# microwaveBoardSimple.net
KiCad netlist of a schematic drawn in Altium Designer
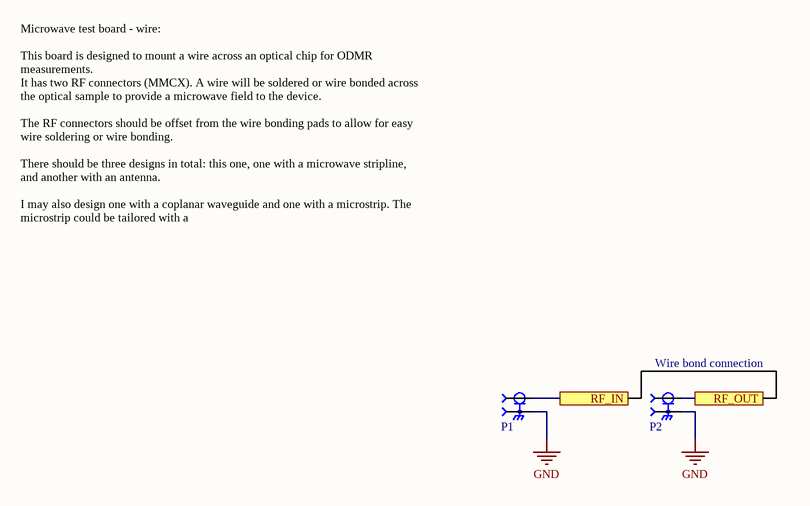
[diagram p0: microwaveBoardSimple.SchDoc]

(export (version "E")
  (design (tool "Eeschema 10.0.6"))
  (components
    (comp (ref "P1")
      (value "MMCXV-J-P-HF-ST-EM1")
      (footprint "MMCXV-J-P-HF-ST-EM1")
      (description "50 OHM MMCX HIGH-VIBRATION JACK,")
      (fields (field (name "PART NUMBER") "PXX-SAM-00013") (field (name "PUBLISHER") "AlbertaSat"))
      (libsource (lib "Database") (part "MMCXV-J-P-HF-ST-EM1"))
    )
    (comp (ref "P2")
      (value "MMCXV-J-P-HF-ST-EM1")
      (footprint "MMCXV-J-P-HF-ST-EM1")
      (description "50 OHM MMCX HIGH-VIBRATION JACK,")
      (fields (field (name "PART NUMBER") "PXX-SAM-00013") (field (name "PUBLISHER") "AlbertaSat"))
      (libsource (lib "Database") (part "MMCXV-J-P-HF-ST-EM1"))
    )
  )
  (nets
    (net (code "1") (name "/RF_IN") (class "Default")
      (node (ref "P1") (pin "1") (pinfunction "1_1") (pintype "passive"))
    )
    (net (code "2") (name "/RF_OUT") (class "Default")
      (node (ref "P2") (pin "1") (pinfunction "1_1") (pintype "passive"))
    )
    (net (code "3") (name "GND") (class "Default")
      (node (ref "P1") (pin "2") (pinfunction "2_2") (pintype "passive"))
      (node (ref "P2") (pin "2") (pinfunction "2_2") (pintype "passive"))
    )
  )
)
